# ESP32-C3-MINI-1_Module.net
KiCad netlist of a schematic drawn in Altium Designer
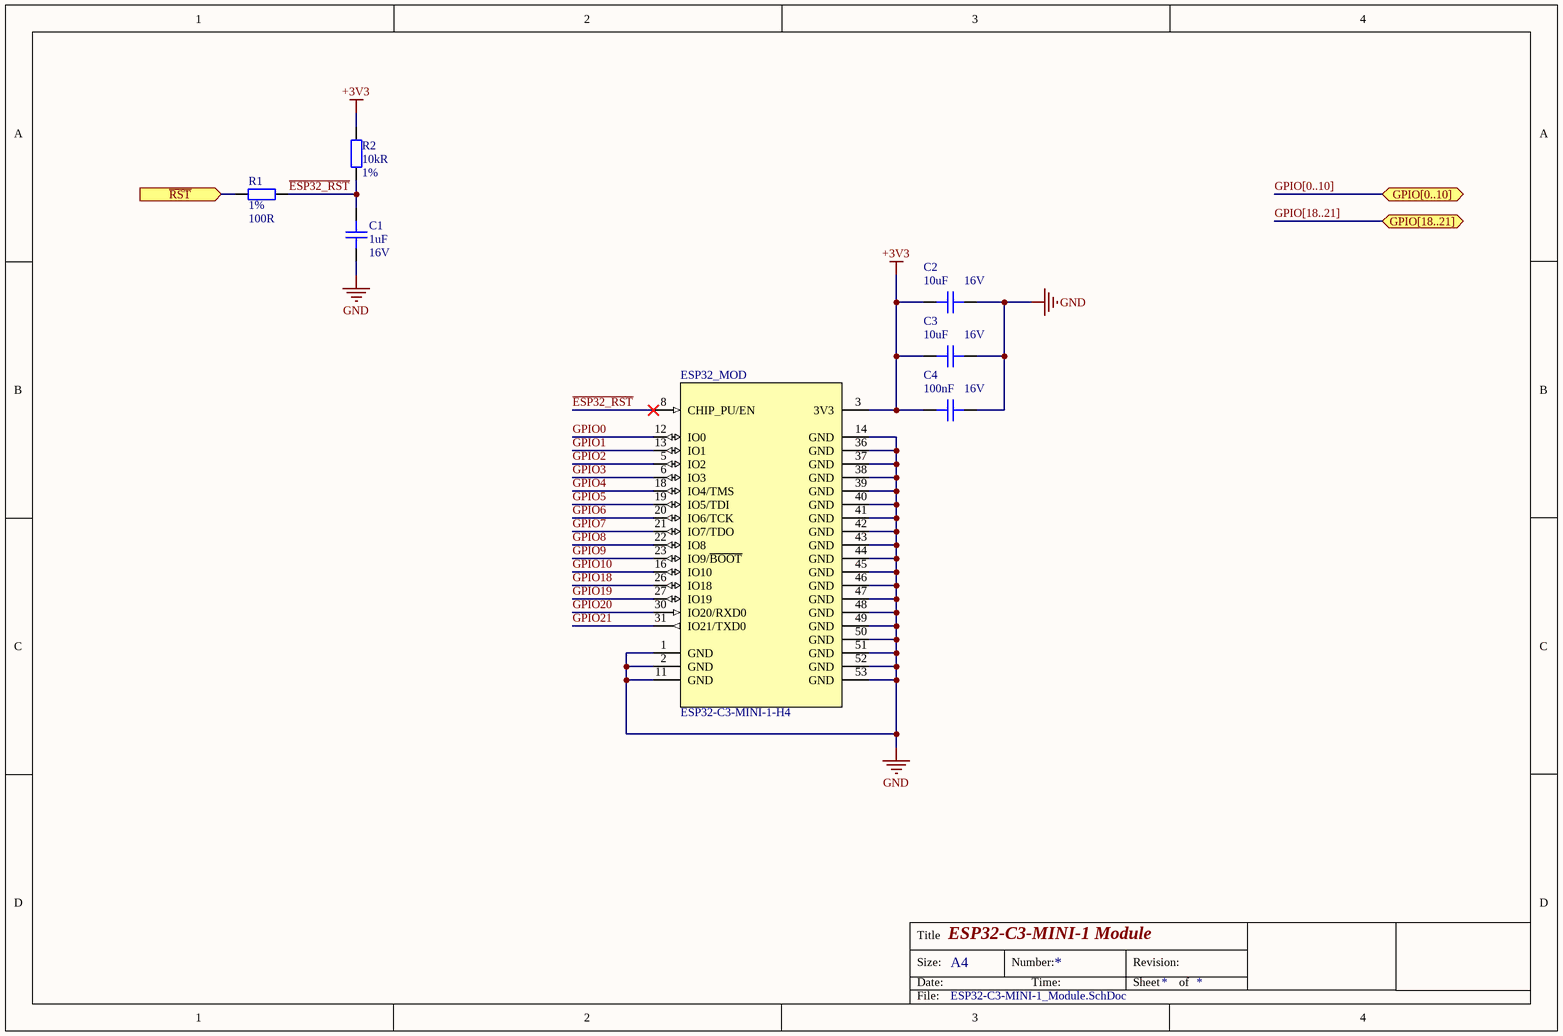
[diagram p0: ESP32-C3-MINI-1_Module.SchDoc]

(export (version "E")
  (design (tool "Eeschema 10.0.6"))
  (components
    (comp (ref "C1")
      (value "CAP CER 1UF 16V X5R 0402")
      (footprint "C0402")
      (description "1µF ±10% 16V Ceramic Capacitor X5R 0402 (1005 Metric)")
      (fields
        (field (name "MANUFACTURER PART NUMBER") "CC0402KRX5R7BB105")
        (field (name "MANUFACTURER") "Yageo")
        (field (name "CAPACITANCE") "1uF")
        (field (name "VOLTAGE RATING") "16V")
      )
      (libsource (lib "capacitors_smd") (part "CAP CER 1UF 16V X5R 0402"))
    )
    (comp (ref "C2")
      (value "CAP CER 10UF 16V X5R 0603")
      (footprint "C0603")
      (description "10µF ±10% 16V Ceramic Capacitor X5R 0603 (1608 Metric)")
      (fields
        (field (name "MANUFACTURER") "Murata")
        (field (name "MANUFACTURER PART NUMBER") "GRM188R61C106KAALJ")
        (field (name "CAPACITANCE") "10uF")
        (field (name "VOLTAGE RATING") "16V")
      )
      (libsource (lib "capacitors_smd") (part "CAP CER 10UF 16V X5R 0603"))
    )
    (comp (ref "C3")
      (value "CAP CER 10UF 16V X5R 0603")
      (footprint "C0603")
      (description "10µF ±10% 16V Ceramic Capacitor X5R 0603 (1608 Metric)")
      (fields
        (field (name "MANUFACTURER") "Murata")
        (field (name "MANUFACTURER PART NUMBER") "GRM188R61C106KAALJ")
        (field (name "CAPACITANCE") "10uF")
        (field (name "VOLTAGE RATING") "16V")
      )
      (libsource (lib "capacitors_smd") (part "CAP CER 10UF 16V X5R 0603"))
    )
    (comp (ref "C4")
      (value "CAP CER 0.1UF 16V X7R 0402")
      (footprint "C0402")
      (description "0.1µF ±10% 16V Ceramic Capacitor X7R 0402 (1005 Metric)")
      (fields
        (field (name "MANUFACTURER PART NUMBER") "CC0402KRX7R7BB104")
        (field (name "MANUFACTURER") "Yageo")
        (field (name "CAPACITANCE") "100nF")
        (field (name "VOLTAGE") "16V")
      )
      (libsource (lib "capacitors_smd") (part "CAP CER 0.1UF 16V X7R 0402"))
    )
    (comp (ref "ESP32_MOD")
      (value "ESP32-C3-MINI-1-H4")
      (footprint "MODULE_ESP32-C3-MINI-1")
      (fields (field (name "MANUFACTURER") "Espressif Systems"))
      (libsource (lib "BLDC_Motor_Driver") (part "MOD ESP32-C3-MINI-1-H4, ESP32-C3FH4, PCB ANT"))
    )
    (comp (ref "R1")
      (value "RES SMD 100 OHM 1% 1/16W 0402")
      (footprint "R0402")
      (description "100 Ohms ±1% 0.063W, 1/16W Chip Resistor 0402 (1005 Metric) Moisture Resistant Thick Film")
      (fields
        (field (name "MANUFACTURER PART NUMBER") "RC0402FR-07100RL")
        (field (name "MANUFACTURER") "Yageo")
        (field (name "TOLERANCE") "1%")
        (field (name "RESISTANCE") "100R")
      )
      (libsource (lib "resistors_smd") (part "RES SMD 100 OHM 1% 1/16W 0402"))
    )
    (comp (ref "R2")
      (value "RES SMD 10K OHM 1% 1/16W 0402")
      (footprint "R0402")
      (description "10 kOhms ±1% 0.063W, 1/16W Chip Resistor 0402 (1005 Metric) Moisture Resistant Thick Film")
      (fields
        (field (name "MANUFACTURER PART NUMBER") "RC0402FR-0710KP")
        (field (name "MANUFACTURER") "Yageo")
        (field (name "RESISTANCE") "10kR")
        (field (name "TOLERANCE") "1%")
      )
      (libsource (lib "resistors_smd") (part "RES SMD 10K OHM 1% 1/16W 0402"))
    )
  )
  (nets
    (net (code "1") (name "+3V3") (class "Default")
      (node (ref "C2") (pin "2") (pinfunction "2_2") (pintype "passive"))
      (node (ref "C3") (pin "2") (pinfunction "2_2") (pintype "passive"))
      (node (ref "C4") (pin "2") (pinfunction "2_2") (pintype "passive"))
      (node (ref "ESP32_MOD") (pin "3") (pinfunction "3V3_3") (pintype "power_in"))
      (node (ref "R2") (pin "1") (pinfunction "1_1") (pintype "passive"))
    )
    (net (code "2") (name "/ESP32_RST") (class "Default")
      (node (ref "C1") (pin "2") (pinfunction "2_2") (pintype "passive"))
      (node (ref "ESP32_MOD") (pin "8") (pinfunction "CHIP_PU/EN_8") (pintype "input"))
      (node (ref "R1") (pin "1") (pinfunction "1_1") (pintype "passive"))
      (node (ref "R2") (pin "2") (pinfunction "2_2") (pintype "passive"))
    )
    (net (code "3") (name "/GPIO0") (class "Default")
      (node (ref "ESP32_MOD") (pin "12") (pinfunction "IO0_12") (pintype "bidirectional"))
    )
    (net (code "4") (name "/GPIO1") (class "Default")
      (node (ref "ESP32_MOD") (pin "13") (pinfunction "IO1_13") (pintype "bidirectional"))
    )
    (net (code "5") (name "/GPIO2") (class "Default")
      (node (ref "ESP32_MOD") (pin "5") (pinfunction "IO2_5") (pintype "bidirectional"))
    )
    (net (code "6") (name "/GPIO3") (class "Default")
      (node (ref "ESP32_MOD") (pin "6") (pinfunction "IO3_6") (pintype "bidirectional"))
    )
    (net (code "7") (name "/GPIO4") (class "Default")
      (node (ref "ESP32_MOD") (pin "18") (pinfunction "IO4/TMS_18") (pintype "bidirectional"))
    )
    (net (code "8") (name "/GPIO5") (class "Default")
      (node (ref "ESP32_MOD") (pin "19") (pinfunction "IO5/TDI_19") (pintype "bidirectional"))
    )
    (net (code "9") (name "/GPIO6") (class "Default")
      (node (ref "ESP32_MOD") (pin "20") (pinfunction "IO6/TCK_20") (pintype "bidirectional"))
    )
    (net (code "10") (name "/GPIO7") (class "Default")
      (node (ref "ESP32_MOD") (pin "21") (pinfunction "IO7/TDO_21") (pintype "bidirectional"))
    )
    (net (code "11") (name "/GPIO8") (class "Default")
      (node (ref "ESP32_MOD") (pin "22") (pinfunction "IO8_22") (pintype "bidirectional"))
    )
    (net (code "12") (name "/GPIO9") (class "Default")
      (node (ref "ESP32_MOD") (pin "23") (pinfunction "IO9/~{BOOT}_23") (pintype "bidirectional"))
    )
    (net (code "13") (name "/GPIO10") (class "Default")
      (node (ref "ESP32_MOD") (pin "16") (pinfunction "IO10_16") (pintype "bidirectional"))
    )
    (net (code "14") (name "/GPIO18") (class "Default")
      (node (ref "ESP32_MOD") (pin "26") (pinfunction "IO18_26") (pintype "bidirectional"))
    )
    (net (code "15") (name "/GPIO19") (class "Default")
      (node (ref "ESP32_MOD") (pin "27") (pinfunction "IO19_27") (pintype "bidirectional"))
    )
    (net (code "16") (name "/GPIO20") (class "Default")
      (node (ref "ESP32_MOD") (pin "30") (pinfunction "IO20/RXD0_30") (pintype "input"))
    )
    (net (code "17") (name "/GPIO21") (class "Default")
      (node (ref "ESP32_MOD") (pin "31") (pinfunction "IO21/TXD0_31") (pintype "output"))
    )
    (net (code "20") (name "/RST") (class "Default")
      (node (ref "R1") (pin "2") (pinfunction "2_2") (pintype "passive"))
    )
    (net (code "21") (name "GND") (class "Default")
      (node (ref "C1") (pin "1") (pinfunction "1_1") (pintype "passive"))
      (node (ref "C2") (pin "1") (pinfunction "1_1") (pintype "passive"))
      (node (ref "C3") (pin "1") (pinfunction "1_1") (pintype "passive"))
      (node (ref "C4") (pin "1") (pinfunction "1_1") (pintype "passive"))
      (node (ref "ESP32_MOD") (pin "1") (pinfunction "GND_1") (pintype "power_in"))
      (node (ref "ESP32_MOD") (pin "11") (pinfunction "GND_11") (pintype "power_in"))
      (node (ref "ESP32_MOD") (pin "14") (pinfunction "GND_14") (pintype "power_in"))
      (node (ref "ESP32_MOD") (pin "2") (pinfunction "GND_2") (pintype "power_in"))
      (node (ref "ESP32_MOD") (pin "36") (pinfunction "GND_36") (pintype "power_in"))
      (node (ref "ESP32_MOD") (pin "37") (pinfunction "GND_37") (pintype "power_in"))
      (node (ref "ESP32_MOD") (pin "38") (pinfunction "GND_38") (pintype "power_in"))
      (node (ref "ESP32_MOD") (pin "39") (pinfunction "GND_39") (pintype "power_in"))
      (node (ref "ESP32_MOD") (pin "40") (pinfunction "GND_40") (pintype "power_in"))
      (node (ref "ESP32_MOD") (pin "41") (pinfunction "GND_41") (pintype "power_in"))
      (node (ref "ESP32_MOD") (pin "42") (pinfunction "GND_42") (pintype "power_in"))
      (node (ref "ESP32_MOD") (pin "43") (pinfunction "GND_43") (pintype "power_in"))
      (node (ref "ESP32_MOD") (pin "44") (pinfunction "GND_44") (pintype "power_in"))
      (node (ref "ESP32_MOD") (pin "45") (pinfunction "GND_45") (pintype "power_in"))
      (node (ref "ESP32_MOD") (pin "46") (pinfunction "GND_46") (pintype "power_in"))
      (node (ref "ESP32_MOD") (pin "47") (pinfunction "GND_47") (pintype "power_in"))
      (node (ref "ESP32_MOD") (pin "48") (pinfunction "GND_48") (pintype "power_in"))
      (node (ref "ESP32_MOD") (pin "49") (pinfunction "GND_49") (pintype "power_in"))
      (node (ref "ESP32_MOD") (pin "50") (pinfunction "GND_50") (pintype "power_in"))
      (node (ref "ESP32_MOD") (pin "51") (pinfunction "GND_51") (pintype "power_in"))
      (node (ref "ESP32_MOD") (pin "52") (pinfunction "GND_52") (pintype "power_in"))
      (node (ref "ESP32_MOD") (pin "53") (pinfunction "GND_53") (pintype "power_in"))
    )
    (net (code "22") (name "unconnected-(ESP32_MOD-NC-Pad4)") (class "Default")
      (node (ref "ESP32_MOD") (pin "4") (pinfunction "NC_4") (pintype "passive"))
    )
    (net (code "23") (name "unconnected-(ESP32_MOD-NC-Pad7)") (class "Default")
      (node (ref "ESP32_MOD") (pin "7") (pinfunction "NC_7") (pintype "passive"))
    )
    (net (code "24") (name "unconnected-(ESP32_MOD-NC-Pad9)") (class "Default")
      (node (ref "ESP32_MOD") (pin "9") (pinfunction "NC_9") (pintype "passive"))
    )
    (net (code "25") (name "unconnected-(ESP32_MOD-NC-Pad10)") (class "Default")
      (node (ref "ESP32_MOD") (pin "10") (pinfunction "NC_10") (pintype "passive"))
    )
    (net (code "26") (name "unconnected-(ESP32_MOD-NC-Pad15)") (class "Default")
      (node (ref "ESP32_MOD") (pin "15") (pinfunction "NC_15") (pintype "passive"))
    )
    (net (code "27") (name "unconnected-(ESP32_MOD-NC-Pad17)") (class "Default")
      (node (ref "ESP32_MOD") (pin "17") (pinfunction "NC_17") (pintype "passive"))
    )
    (net (code "28") (name "unconnected-(ESP32_MOD-NC-Pad24)") (class "Default")
      (node (ref "ESP32_MOD") (pin "24") (pinfunction "NC_24") (pintype "passive"))
    )
    (net (code "29") (name "unconnected-(ESP32_MOD-NC-Pad25)") (class "Default")
      (node (ref "ESP32_MOD") (pin "25") (pinfunction "NC_25") (pintype "passive"))
    )
    (net (code "30") (name "unconnected-(ESP32_MOD-NC-Pad28)") (class "Default")
      (node (ref "ESP32_MOD") (pin "28") (pinfunction "NC_28") (pintype "passive"))
    )
    (net (code "31") (name "unconnected-(ESP32_MOD-NC-Pad29)") (class "Default")
      (node (ref "ESP32_MOD") (pin "29") (pinfunction "NC_29") (pintype "passive"))
    )
    (net (code "32") (name "unconnected-(ESP32_MOD-NC-Pad32)") (class "Default")
      (node (ref "ESP32_MOD") (pin "32") (pinfunction "NC_32") (pintype "passive"))
    )
    (net (code "33") (name "unconnected-(ESP32_MOD-NC-Pad33)") (class "Default")
      (node (ref "ESP32_MOD") (pin "33") (pinfunction "NC_33") (pintype "passive"))
    )
    (net (code "34") (name "unconnected-(ESP32_MOD-NC-Pad34)") (class "Default")
      (node (ref "ESP32_MOD") (pin "34") (pinfunction "NC_34") (pintype "passive"))
    )
    (net (code "35") (name "unconnected-(ESP32_MOD-NC-Pad35)") (class "Default")
      (node (ref "ESP32_MOD") (pin "35") (pinfunction "NC_35") (pintype "passive"))
    )
  )
)
